# MC33932_H-Bridge.net
KiCad netlist of a schematic drawn in EAGLE
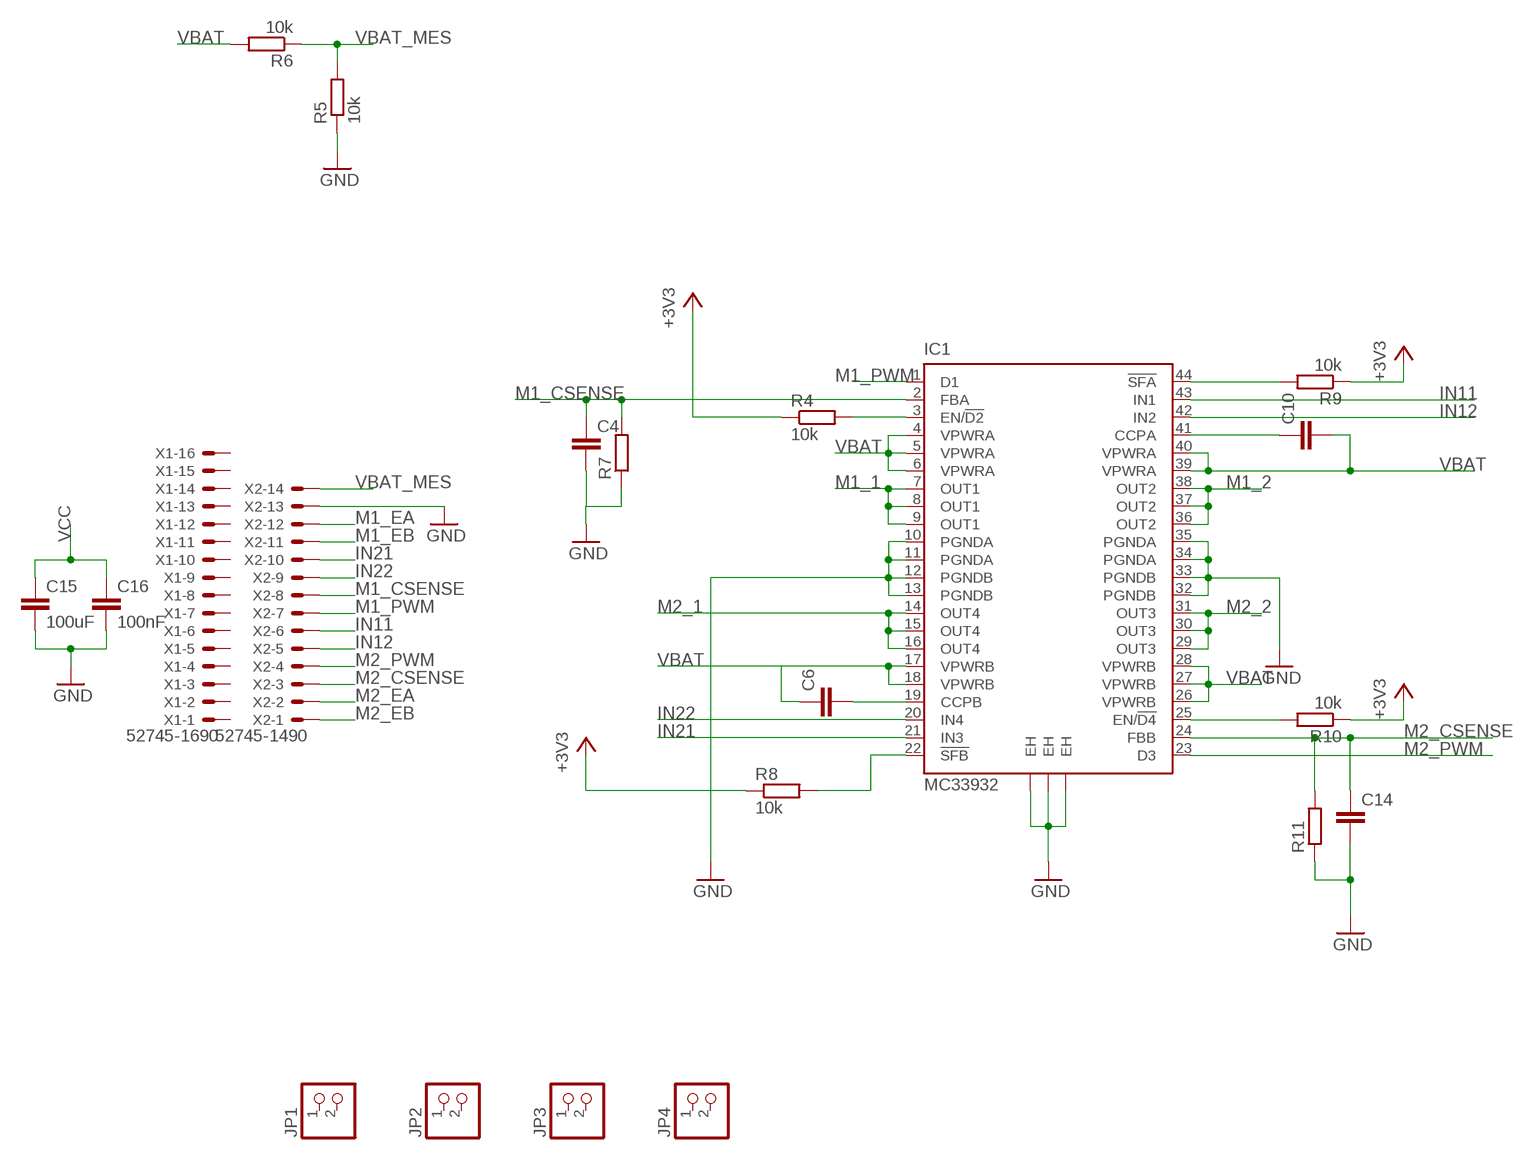
[diagram p0: schematic, sheet 1]

(export (version "E")
  (design (tool "Eeschema 10.0.6"))
  (components
    (comp (ref "C4")
      (value "C-EUC0603")
      (footprint "eagle-import:C0603")
      (libsource (lib "eagle-import") (part "C-EUC0603"))
    )
    (comp (ref "C6")
      (value "C-EUC0805")
      (footprint "eagle-import:C0805")
      (libsource (lib "eagle-import") (part "C-EUC0805"))
    )
    (comp (ref "C10")
      (value "C-EUC0805")
      (footprint "eagle-import:C0805")
      (libsource (lib "eagle-import") (part "C-EUC0805"))
    )
    (comp (ref "C14")
      (value "C-EUC0603")
      (footprint "eagle-import:C0603")
      (libsource (lib "eagle-import") (part "C-EUC0603"))
    )
    (comp (ref "C15")
      (value "100uF")
      (footprint "eagle-import:C1210K")
      (libsource (lib "eagle-import") (part "C-EUC1210K"))
    )
    (comp (ref "C16")
      (value "100nF")
      (footprint "eagle-import:C0603")
      (libsource (lib "eagle-import") (part "C-EUC0603"))
    )
    (comp (ref "IC1")
      (value "MC33932")
      (footprint "eagle-import:HSOP44")
      (fields (field (name "MPN") "MC33932VW"))
      (libsource (lib "eagle-import") (part "MC33932"))
    )
    (comp (ref "JP1")
      (value "PINHD-1X2")
      (footprint "eagle-import:1X02")
      (libsource (lib "eagle-import") (part "PINHD-1X2"))
    )
    (comp (ref "JP2")
      (value "PINHD-1X2")
      (footprint "eagle-import:1X02")
      (libsource (lib "eagle-import") (part "PINHD-1X2"))
    )
    (comp (ref "JP3")
      (value "PINHD-1X2")
      (footprint "eagle-import:1X02")
      (libsource (lib "eagle-import") (part "PINHD-1X2"))
    )
    (comp (ref "JP4")
      (value "PINHD-1X2")
      (footprint "eagle-import:1X02")
      (libsource (lib "eagle-import") (part "PINHD-1X2"))
    )
    (comp (ref "R4")
      (value "10k")
      (footprint "eagle-import:R0603")
      (libsource (lib "eagle-import") (part "R-EU_R0603"))
    )
    (comp (ref "R5")
      (value "10k")
      (footprint "eagle-import:R0603")
      (libsource (lib "eagle-import") (part "R-EU_R0603"))
    )
    (comp (ref "R6")
      (value "10k")
      (footprint "eagle-import:R0603")
      (libsource (lib "eagle-import") (part "R-EU_R0603"))
    )
    (comp (ref "R7")
      (value "R-EU_R0603")
      (footprint "eagle-import:R0603")
      (libsource (lib "eagle-import") (part "R-EU_R0603"))
    )
    (comp (ref "R8")
      (value "10k")
      (footprint "eagle-import:R0603")
      (libsource (lib "eagle-import") (part "R-EU_R0603"))
    )
    (comp (ref "R9")
      (value "10k")
      (footprint "eagle-import:R0603")
      (libsource (lib "eagle-import") (part "R-EU_R0603"))
    )
    (comp (ref "R10")
      (value "10k")
      (footprint "eagle-import:R0603")
      (libsource (lib "eagle-import") (part "R-EU_R0603"))
    )
    (comp (ref "R11")
      (value "R-EU_R0603")
      (footprint "eagle-import:R0603")
      (libsource (lib "eagle-import") (part "R-EU_R0603"))
    )
    (comp (ref "X1")
      (value "52745-1690")
      (footprint "eagle-import:52745-1690")
      (fields (field (name "MF") "MOLEX"))
      (libsource (lib "eagle-import") (part "52745-1690"))
    )
    (comp (ref "X2")
      (value "52745-1490")
      (footprint "eagle-import:52745-1490")
      (fields (field (name "MF") "WALDOM/MOLEX"))
      (libsource (lib "eagle-import") (part "52745-1490"))
    )
  )
  (nets
    (net (code "1") (name "+3V3") (class "Default")
      (node (ref "R10") (pin "1") (pinfunction "1_1") (pintype "passive"))
      (node (ref "R4") (pin "1") (pinfunction "1_1") (pintype "passive"))
      (node (ref "R8") (pin "1") (pinfunction "1_1") (pintype "passive"))
      (node (ref "R9") (pin "1") (pinfunction "1_1") (pintype "passive"))
    )
    (net (code "2") (name "/IN11") (class "Default")
      (node (ref "IC1") (pin "43") (pinfunction "IN1_43") (pintype "input"))
      (node (ref "X2") (pin "6") (pinfunction "S_6") (pintype "passive"))
    )
    (net (code "3") (name "/IN12") (class "Default")
      (node (ref "IC1") (pin "42") (pinfunction "IN2_42") (pintype "input"))
      (node (ref "X2") (pin "5") (pinfunction "S_5") (pintype "passive"))
    )
    (net (code "4") (name "/IN21") (class "Default")
      (node (ref "IC1") (pin "21") (pinfunction "IN3_21") (pintype "input"))
      (node (ref "X2") (pin "10") (pinfunction "S_10") (pintype "passive"))
    )
    (net (code "5") (name "/IN22") (class "Default")
      (node (ref "IC1") (pin "20") (pinfunction "IN4_20") (pintype "input"))
      (node (ref "X2") (pin "9") (pinfunction "S_9") (pintype "passive"))
    )
    (net (code "6") (name "/M1_1") (class "Default")
      (node (ref "IC1") (pin "7") (pinfunction "OUT1_7") (pintype "output"))
      (node (ref "IC1") (pin "8") (pinfunction "OUT1_8") (pintype "passive"))
      (node (ref "IC1") (pin "9") (pinfunction "OUT1_9") (pintype "passive"))
    )
    (net (code "7") (name "/M1_2") (class "Default")
      (node (ref "IC1") (pin "36") (pinfunction "OUT2_36") (pintype "output"))
      (node (ref "IC1") (pin "37") (pinfunction "OUT2_37") (pintype "passive"))
      (node (ref "IC1") (pin "38") (pinfunction "OUT2_38") (pintype "passive"))
    )
    (net (code "8") (name "/M1_CSENSE") (class "Default")
      (node (ref "C4") (pin "1") (pinfunction "1_1") (pintype "passive"))
      (node (ref "IC1") (pin "2") (pinfunction "FBA_2") (pintype "output"))
      (node (ref "R7") (pin "2") (pinfunction "2_2") (pintype "passive"))
      (node (ref "X2") (pin "8") (pinfunction "S_8") (pintype "passive"))
    )
    (net (code "9") (name "/M1_EA") (class "Default")
      (node (ref "X2") (pin "12") (pinfunction "S_12") (pintype "passive"))
    )
    (net (code "10") (name "/M1_EB") (class "Default")
      (node (ref "X2") (pin "11") (pinfunction "S_11") (pintype "passive"))
    )
    (net (code "11") (name "/M1_PWM") (class "Default")
      (node (ref "IC1") (pin "1") (pinfunction "D1_1") (pintype "input"))
      (node (ref "X2") (pin "7") (pinfunction "S_7") (pintype "passive"))
    )
    (net (code "12") (name "/M2_1") (class "Default")
      (node (ref "IC1") (pin "14") (pinfunction "OUT4_14") (pintype "output"))
      (node (ref "IC1") (pin "15") (pinfunction "OUT4_15") (pintype "passive"))
      (node (ref "IC1") (pin "16") (pinfunction "OUT4_16") (pintype "passive"))
    )
    (net (code "13") (name "/M2_2") (class "Default")
      (node (ref "IC1") (pin "29") (pinfunction "OUT3_29") (pintype "output"))
      (node (ref "IC1") (pin "30") (pinfunction "OUT3_30") (pintype "passive"))
      (node (ref "IC1") (pin "31") (pinfunction "OUT3_31") (pintype "passive"))
    )
    (net (code "14") (name "/M2_CSENSE") (class "Default")
      (node (ref "C14") (pin "1") (pinfunction "1_1") (pintype "passive"))
      (node (ref "IC1") (pin "24") (pinfunction "FBB_24") (pintype "output"))
      (node (ref "R11") (pin "2") (pinfunction "2_2") (pintype "passive"))
      (node (ref "X2") (pin "3") (pinfunction "S_3") (pintype "passive"))
    )
    (net (code "15") (name "/M2_EA") (class "Default")
      (node (ref "X2") (pin "2") (pinfunction "S_2") (pintype "passive"))
    )
    (net (code "16") (name "/M2_EB") (class "Default")
      (node (ref "X2") (pin "1") (pinfunction "S_1") (pintype "passive"))
    )
    (net (code "17") (name "/M2_PWM") (class "Default")
      (node (ref "IC1") (pin "23") (pinfunction "D3_23") (pintype "input"))
      (node (ref "X2") (pin "4") (pinfunction "S_4") (pintype "passive"))
    )
    (net (code "18") (name "/VBAT") (class "Default")
      (node (ref "C10") (pin "2") (pinfunction "2_2") (pintype "passive"))
      (node (ref "C6") (pin "1") (pinfunction "1_1") (pintype "passive"))
      (node (ref "IC1") (pin "17") (pinfunction "VPWRB_17") (pintype "input"))
      (node (ref "IC1") (pin "18") (pinfunction "VPWRB_18") (pintype "input"))
      (node (ref "IC1") (pin "26") (pinfunction "VPWRB_26") (pintype "input"))
      (node (ref "IC1") (pin "27") (pinfunction "VPWRB_27") (pintype "input"))
      (node (ref "IC1") (pin "28") (pinfunction "VPWRB_28") (pintype "input"))
      (node (ref "IC1") (pin "39") (pinfunction "VPWRA_39") (pintype "input"))
      (node (ref "IC1") (pin "4") (pinfunction "VPWRA_4") (pintype "input"))
      (node (ref "IC1") (pin "40") (pinfunction "VPWRA_40") (pintype "input"))
      (node (ref "IC1") (pin "5") (pinfunction "VPWRA_5") (pintype "input"))
      (node (ref "IC1") (pin "6") (pinfunction "VPWRA_6") (pintype "input"))
      (node (ref "R6") (pin "2") (pinfunction "2_2") (pintype "passive"))
    )
    (net (code "19") (name "/VBAT_MES") (class "Default")
      (node (ref "R5") (pin "2") (pinfunction "2_2") (pintype "passive"))
      (node (ref "R6") (pin "1") (pinfunction "1_1") (pintype "passive"))
      (node (ref "X2") (pin "14") (pinfunction "S_14") (pintype "passive"))
    )
    (net (code "20") (name "/VCC") (class "Default")
      (node (ref "C15") (pin "1") (pinfunction "1_1") (pintype "passive"))
      (node (ref "C16") (pin "1") (pinfunction "1_1") (pintype "passive"))
    )
    (net (code "21") (name "GND") (class "Default")
      (node (ref "C14") (pin "2") (pinfunction "2_2") (pintype "passive"))
      (node (ref "C15") (pin "2") (pinfunction "2_2") (pintype "passive"))
      (node (ref "C16") (pin "2") (pinfunction "2_2") (pintype "passive"))
      (node (ref "C4") (pin "2") (pinfunction "2_2") (pintype "passive"))
      (node (ref "IC1") (pin "10") (pinfunction "PGNDA_10") (pintype "power_in"))
      (node (ref "IC1") (pin "11") (pinfunction "PGNDA_11") (pintype "power_in"))
      (node (ref "IC1") (pin "12") (pinfunction "PGNDB_12") (pintype "power_in"))
      (node (ref "IC1") (pin "13") (pinfunction "PGNDB_13") (pintype "power_in"))
      (node (ref "IC1") (pin "32") (pinfunction "PGNDB_32") (pintype "power_in"))
      (node (ref "IC1") (pin "33") (pinfunction "PGNDB_33") (pintype "power_in"))
      (node (ref "IC1") (pin "34") (pinfunction "PGNDA_34") (pintype "power_in"))
      (node (ref "IC1") (pin "35") (pinfunction "PGNDA_35") (pintype "power_in"))
      (node (ref "IC1") (pin "EH@1") (pinfunction "EH_EH@1") (pintype "passive"))
      (node (ref "IC1") (pin "EH@2") (pinfunction "EH_EH@2") (pintype "passive"))
      (node (ref "IC1") (pin "EH@3") (pinfunction "EH_EH@3") (pintype "passive"))
      (node (ref "R11") (pin "1") (pinfunction "1_1") (pintype "passive"))
      (node (ref "R5") (pin "1") (pinfunction "1_1") (pintype "passive"))
      (node (ref "R7") (pin "1") (pinfunction "1_1") (pintype "passive"))
      (node (ref "X2") (pin "13") (pinfunction "S_13") (pintype "passive"))
    )
    (net (code "22") (name "Net-(IC1-CCPA)") (class "Default")
      (node (ref "C10") (pin "1") (pinfunction "1_1") (pintype "passive"))
      (node (ref "IC1") (pin "41") (pinfunction "CCPA_41") (pintype "output"))
    )
    (net (code "23") (name "Net-(IC1-CCPB)") (class "Default")
      (node (ref "C6") (pin "2") (pinfunction "2_2") (pintype "passive"))
      (node (ref "IC1") (pin "19") (pinfunction "CCPB_19") (pintype "output"))
    )
    (net (code "24") (name "Net-(IC1-EN{slash}~{D2})") (class "Default")
      (node (ref "IC1") (pin "3") (pinfunction "EN/~{D2}_3") (pintype "input"))
      (node (ref "R4") (pin "2") (pinfunction "2_2") (pintype "passive"))
    )
    (net (code "25") (name "Net-(IC1-EN{slash}~{D4})") (class "Default")
      (node (ref "IC1") (pin "25") (pinfunction "EN/~{D4}_25") (pintype "input"))
      (node (ref "R10") (pin "2") (pinfunction "2_2") (pintype "passive"))
    )
    (net (code "26") (name "Net-(IC1-~{SFA})") (class "Default")
      (node (ref "IC1") (pin "44") (pinfunction "~{SFA}_44") (pintype "open_collector"))
      (node (ref "R9") (pin "2") (pinfunction "2_2") (pintype "passive"))
    )
    (net (code "27") (name "Net-(IC1-~{SFB})") (class "Default")
      (node (ref "IC1") (pin "22") (pinfunction "~{SFB}_22") (pintype "open_collector"))
      (node (ref "R8") (pin "2") (pinfunction "2_2") (pintype "passive"))
    )
    (net (code "28") (name "unconnected-(JP1-Pad1)") (class "Default")
      (node (ref "JP1") (pin "1") (pinfunction "1_1") (pintype "passive"))
    )
    (net (code "29") (name "unconnected-(JP1-Pad2)") (class "Default")
      (node (ref "JP1") (pin "2") (pinfunction "2_2") (pintype "passive"))
    )
    (net (code "30") (name "unconnected-(JP2-Pad1)") (class "Default")
      (node (ref "JP2") (pin "1") (pinfunction "1_1") (pintype "passive"))
    )
    (net (code "31") (name "unconnected-(JP2-Pad2)") (class "Default")
      (node (ref "JP2") (pin "2") (pinfunction "2_2") (pintype "passive"))
    )
    (net (code "32") (name "unconnected-(JP3-Pad1)") (class "Default")
      (node (ref "JP3") (pin "1") (pinfunction "1_1") (pintype "passive"))
    )
    (net (code "33") (name "unconnected-(JP3-Pad2)") (class "Default")
      (node (ref "JP3") (pin "2") (pinfunction "2_2") (pintype "passive"))
    )
    (net (code "34") (name "unconnected-(JP4-Pad1)") (class "Default")
      (node (ref "JP4") (pin "1") (pinfunction "1_1") (pintype "passive"))
    )
    (net (code "35") (name "unconnected-(JP4-Pad2)") (class "Default")
      (node (ref "JP4") (pin "2") (pinfunction "2_2") (pintype "passive"))
    )
    (net (code "36") (name "unconnected-(X1A-S-Pad1)") (class "Default")
      (node (ref "X1") (pin "1") (pinfunction "S_1") (pintype "passive"))
    )
    (net (code "37") (name "unconnected-(X1B-S-Pad10)") (class "Default")
      (node (ref "X1") (pin "10") (pinfunction "S_10") (pintype "passive"))
    )
    (net (code "38") (name "unconnected-(X1C-S-Pad11)") (class "Default")
      (node (ref "X1") (pin "11") (pinfunction "S_11") (pintype "passive"))
    )
    (net (code "39") (name "unconnected-(X1D-S-Pad12)") (class "Default")
      (node (ref "X1") (pin "12") (pinfunction "S_12") (pintype "passive"))
    )
    (net (code "40") (name "unconnected-(X1E-S-Pad13)") (class "Default")
      (node (ref "X1") (pin "13") (pinfunction "S_13") (pintype "passive"))
    )
    (net (code "41") (name "unconnected-(X1F-S-Pad14)") (class "Default")
      (node (ref "X1") (pin "14") (pinfunction "S_14") (pintype "passive"))
    )
    (net (code "42") (name "unconnected-(X1G-S-Pad15)") (class "Default")
      (node (ref "X1") (pin "15") (pinfunction "S_15") (pintype "passive"))
    )
    (net (code "43") (name "unconnected-(X1H-S-Pad16)") (class "Default")
      (node (ref "X1") (pin "16") (pinfunction "S_16") (pintype "passive"))
    )
    (net (code "44") (name "unconnected-(X1I-S-Pad2)") (class "Default")
      (node (ref "X1") (pin "2") (pinfunction "S_2") (pintype "passive"))
    )
    (net (code "45") (name "unconnected-(X1J-S-Pad3)") (class "Default")
      (node (ref "X1") (pin "3") (pinfunction "S_3") (pintype "passive"))
    )
    (net (code "46") (name "unconnected-(X1K-S-Pad4)") (class "Default")
      (node (ref "X1") (pin "4") (pinfunction "S_4") (pintype "passive"))
    )
    (net (code "47") (name "unconnected-(X1L-S-Pad5)") (class "Default")
      (node (ref "X1") (pin "5") (pinfunction "S_5") (pintype "passive"))
    )
    (net (code "48") (name "unconnected-(X1M-S-Pad6)") (class "Default")
      (node (ref "X1") (pin "6") (pinfunction "S_6") (pintype "passive"))
    )
    (net (code "49") (name "unconnected-(X1N-S-Pad7)") (class "Default")
      (node (ref "X1") (pin "7") (pinfunction "S_7") (pintype "passive"))
    )
    (net (code "50") (name "unconnected-(X1O-S-Pad8)") (class "Default")
      (node (ref "X1") (pin "8") (pinfunction "S_8") (pintype "passive"))
    )
    (net (code "51") (name "unconnected-(X1P-S-Pad9)") (class "Default")
      (node (ref "X1") (pin "9") (pinfunction "S_9") (pintype "passive"))
    )
  )
)
